# hand_master_v0.net
KiCad netlist of a schematic drawn in EAGLE
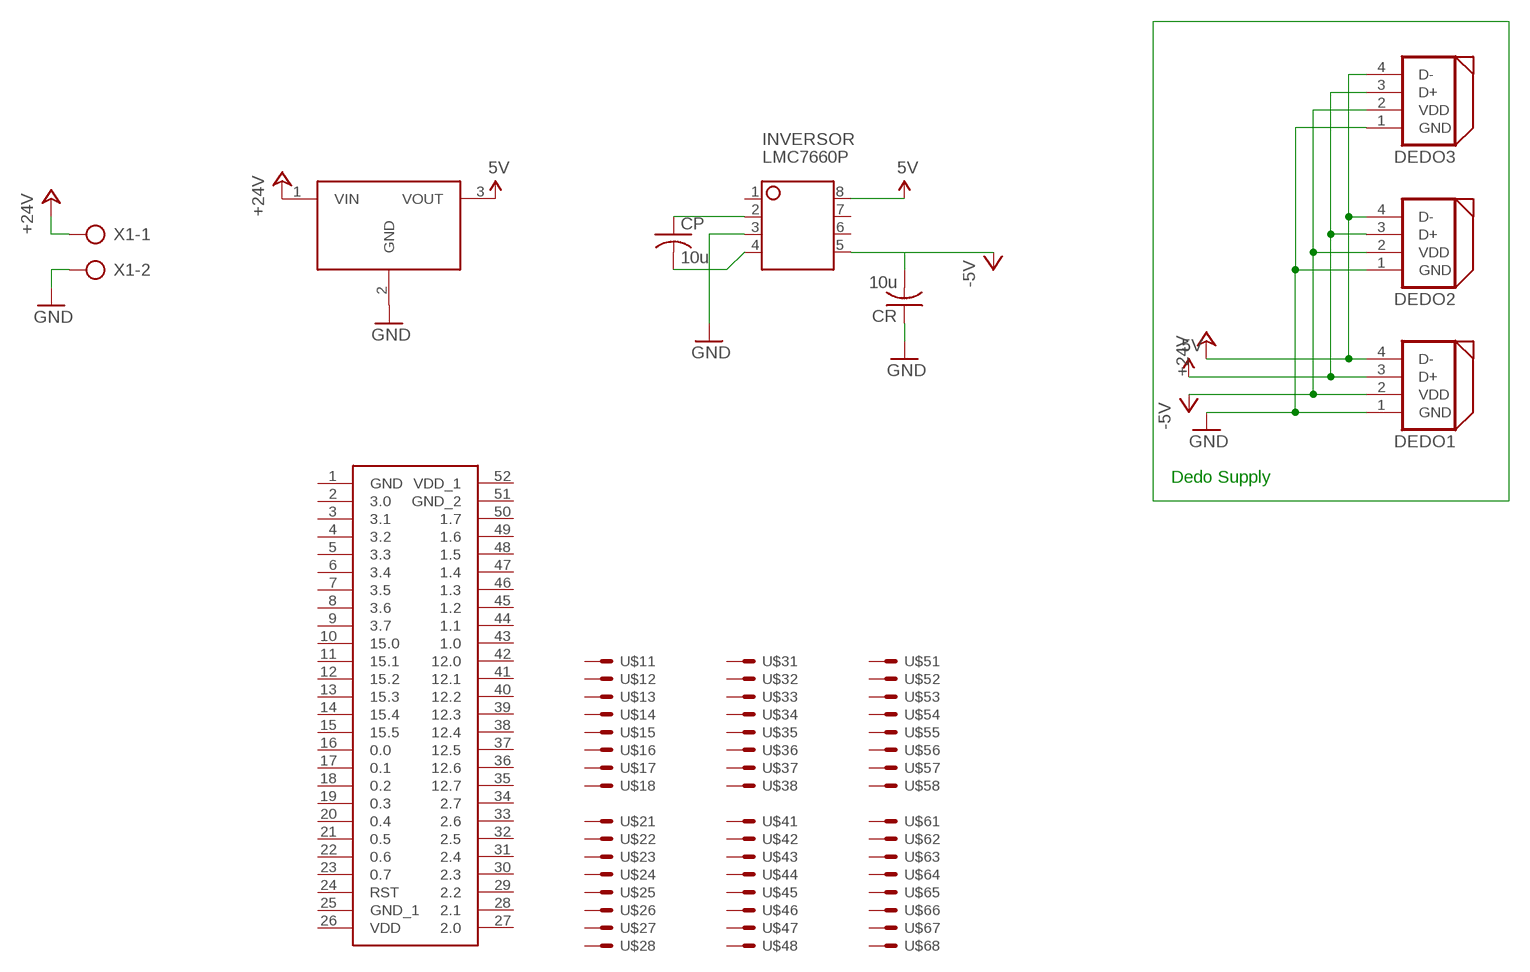
[diagram p0: schematic, sheet 1]

(export (version "E")
  (design (tool "Eeschema 10.0.6"))
  (components
    (comp (ref "CP")
      (value "10u")
      (footprint "eagle-import:C025-025X050")
      (libsource (lib "eagle-import") (part "C-US025-025X050"))
    )
    (comp (ref "CR")
      (value "10u")
      (footprint "eagle-import:C025-025X050")
      (libsource (lib "eagle-import") (part "C-US025-025X050"))
    )
    (comp (ref "DEDO1")
      (value "DYNAMIXEL_RS485")
      (footprint "eagle-import:DYNAMIXEL_SPOX_04")
      (libsource (lib "eagle-import") (part "DYNAMIXEL_RS485"))
    )
    (comp (ref "DEDO2")
      (value "DYNAMIXEL_RS485")
      (footprint "eagle-import:DYNAMIXEL_SPOX_04")
      (libsource (lib "eagle-import") (part "DYNAMIXEL_RS485"))
    )
    (comp (ref "DEDO3")
      (value "DYNAMIXEL_RS485")
      (footprint "eagle-import:DYNAMIXEL_SPOX_04")
      (libsource (lib "eagle-import") (part "DYNAMIXEL_RS485"))
    )
    (comp (ref "INVERSOR")
      (value "LMC7660P")
      (footprint "eagle-import:DIL08")
      (libsource (lib "eagle-import") (part "LMC7660P"))
    )
    (comp (ref "POWER_SUPPLY")
      (value "TSR-1")
      (footprint "eagle-import:TO220V")
      (libsource (lib "eagle-import") (part "TSR-1"))
    )
    (comp (ref "U$1")
      (value "JST8")
      (footprint "eagle-import:JST")
      (libsource (lib "eagle-import") (part "JST8"))
    )
    (comp (ref "U$2")
      (value "JST8")
      (footprint "eagle-import:JST")
      (libsource (lib "eagle-import") (part "JST8"))
    )
    (comp (ref "U$3")
      (value "JST8")
      (footprint "eagle-import:JST")
      (libsource (lib "eagle-import") (part "JST8"))
    )
    (comp (ref "U$4")
      (value "JST8")
      (footprint "eagle-import:JST")
      (libsource (lib "eagle-import") (part "JST8"))
    )
    (comp (ref "U$5")
      (value "JST8")
      (footprint "eagle-import:JST")
      (libsource (lib "eagle-import") (part "JST8"))
    )
    (comp (ref "U$6")
      (value "JST8")
      (footprint "eagle-import:JST")
      (libsource (lib "eagle-import") (part "JST8"))
    )
    (comp (ref "U$7")
      (value "CY8CKIT-059")
      (footprint "eagle-import:CY8CKIT-059")
      (libsource (lib "eagle-import") (part "CY8CKIT-059"))
    )
    (comp (ref "X1")
      (value "AK500/2")
      (footprint "eagle-import:AK500_2")
      (libsource (lib "eagle-import") (part "AK500/2"))
    )
  )
  (nets
    (net (code "1") (name "+24V") (class "Default")
      (node (ref "DEDO1") (pin "4") (pinfunction "D-_4") (pintype "bidirectional"))
      (node (ref "DEDO2") (pin "4") (pinfunction "D-_4") (pintype "bidirectional"))
      (node (ref "DEDO3") (pin "4") (pinfunction "D-_4") (pintype "bidirectional"))
      (node (ref "POWER_SUPPLY") (pin "1") (pinfunction "VIN_1") (pintype "bidirectional"))
      (node (ref "X1") (pin "1") (pinfunction "KL_1") (pintype "passive"))
    )
    (net (code "2") (name "-5V") (class "Default")
      (node (ref "CR") (pin "2") (pinfunction "2_2") (pintype "passive"))
      (node (ref "DEDO1") (pin "2") (pinfunction "VDD_2") (pintype "power_in"))
      (node (ref "DEDO2") (pin "2") (pinfunction "VDD_2") (pintype "power_in"))
      (node (ref "DEDO3") (pin "2") (pinfunction "VDD_2") (pintype "power_in"))
      (node (ref "INVERSOR") (pin "5") (pinfunction "VOUT_5") (pintype "bidirectional"))
    )
    (net (code "3") (name "5V") (class "Default")
      (node (ref "DEDO1") (pin "3") (pinfunction "D+_3") (pintype "bidirectional"))
      (node (ref "DEDO2") (pin "3") (pinfunction "D+_3") (pintype "bidirectional"))
      (node (ref "DEDO3") (pin "3") (pinfunction "D+_3") (pintype "bidirectional"))
      (node (ref "INVERSOR") (pin "8") (pinfunction "V+_8") (pintype "bidirectional"))
      (node (ref "POWER_SUPPLY") (pin "3") (pinfunction "VOUT_3") (pintype "bidirectional"))
    )
    (net (code "4") (name "GND") (class "Default")
      (node (ref "CR") (pin "1") (pinfunction "1_1") (pintype "passive"))
      (node (ref "DEDO1") (pin "1") (pinfunction "GND_1") (pintype "power_in"))
      (node (ref "DEDO2") (pin "1") (pinfunction "GND_1") (pintype "power_in"))
      (node (ref "DEDO3") (pin "1") (pinfunction "GND_1") (pintype "power_in"))
      (node (ref "INVERSOR") (pin "3") (pinfunction "GND_3") (pintype "bidirectional"))
      (node (ref "POWER_SUPPLY") (pin "2") (pinfunction "GND_2") (pintype "bidirectional"))
      (node (ref "X1") (pin "2") (pinfunction "KL_2") (pintype "passive"))
    )
    (net (code "5") (name "Net-(INVERSOR-CAP+)") (class "Default")
      (node (ref "CP") (pin "1") (pinfunction "1_1") (pintype "passive"))
      (node (ref "INVERSOR") (pin "2") (pinfunction "CAP+_2") (pintype "bidirectional"))
    )
    (net (code "6") (name "Net-(INVERSOR-CAP-)") (class "Default")
      (node (ref "CP") (pin "2") (pinfunction "2_2") (pintype "passive"))
      (node (ref "INVERSOR") (pin "4") (pinfunction "CAP-_4") (pintype "bidirectional"))
    )
    (net (code "7") (name "unconnected-(INVERSOR-LV-Pad6)") (class "Default")
      (node (ref "INVERSOR") (pin "6") (pinfunction "LV_6") (pintype "bidirectional"))
    )
    (net (code "8") (name "unconnected-(INVERSOR-N{slash}C-Pad1)") (class "Default")
      (node (ref "INVERSOR") (pin "1") (pinfunction "N/C_1") (pintype "bidirectional"))
    )
    (net (code "9") (name "unconnected-(INVERSOR-OSC-Pad7)") (class "Default")
      (node (ref "INVERSOR") (pin "7") (pinfunction "OSC_7") (pintype "bidirectional"))
    )
    (net (code "10") (name "unconnected-(U$1A-S-Pad1)") (class "Default")
      (node (ref "U$1") (pin "1") (pinfunction "S_1") (pintype "passive"))
    )
    (net (code "11") (name "unconnected-(U$1B-S-Pad2)") (class "Default")
      (node (ref "U$1") (pin "2") (pinfunction "S_2") (pintype "passive"))
    )
    (net (code "12") (name "unconnected-(U$1C-S-Pad3)") (class "Default")
      (node (ref "U$1") (pin "3") (pinfunction "S_3") (pintype "passive"))
    )
    (net (code "13") (name "unconnected-(U$1D-S-Pad4)") (class "Default")
      (node (ref "U$1") (pin "4") (pinfunction "S_4") (pintype "passive"))
    )
    (net (code "14") (name "unconnected-(U$1E-S-Pad5)") (class "Default")
      (node (ref "U$1") (pin "5") (pinfunction "S_5") (pintype "passive"))
    )
    (net (code "15") (name "unconnected-(U$1F-S-Pad6)") (class "Default")
      (node (ref "U$1") (pin "6") (pinfunction "S_6") (pintype "passive"))
    )
    (net (code "16") (name "unconnected-(U$1G-S-Pad7)") (class "Default")
      (node (ref "U$1") (pin "7") (pinfunction "S_7") (pintype "passive"))
    )
    (net (code "17") (name "unconnected-(U$1H-S-Pad8)") (class "Default")
      (node (ref "U$1") (pin "8") (pinfunction "S_8") (pintype "passive"))
    )
    (net (code "18") (name "unconnected-(U$2A-S-Pad1)") (class "Default")
      (node (ref "U$2") (pin "1") (pinfunction "S_1") (pintype "passive"))
    )
    (net (code "19") (name "unconnected-(U$2B-S-Pad2)") (class "Default")
      (node (ref "U$2") (pin "2") (pinfunction "S_2") (pintype "passive"))
    )
    (net (code "20") (name "unconnected-(U$2C-S-Pad3)") (class "Default")
      (node (ref "U$2") (pin "3") (pinfunction "S_3") (pintype "passive"))
    )
    (net (code "21") (name "unconnected-(U$2D-S-Pad4)") (class "Default")
      (node (ref "U$2") (pin "4") (pinfunction "S_4") (pintype "passive"))
    )
    (net (code "22") (name "unconnected-(U$2E-S-Pad5)") (class "Default")
      (node (ref "U$2") (pin "5") (pinfunction "S_5") (pintype "passive"))
    )
    (net (code "23") (name "unconnected-(U$2F-S-Pad6)") (class "Default")
      (node (ref "U$2") (pin "6") (pinfunction "S_6") (pintype "passive"))
    )
    (net (code "24") (name "unconnected-(U$2G-S-Pad7)") (class "Default")
      (node (ref "U$2") (pin "7") (pinfunction "S_7") (pintype "passive"))
    )
    (net (code "25") (name "unconnected-(U$2H-S-Pad8)") (class "Default")
      (node (ref "U$2") (pin "8") (pinfunction "S_8") (pintype "passive"))
    )
    (net (code "26") (name "unconnected-(U$3A-S-Pad1)") (class "Default")
      (node (ref "U$3") (pin "1") (pinfunction "S_1") (pintype "passive"))
    )
    (net (code "27") (name "unconnected-(U$3B-S-Pad2)") (class "Default")
      (node (ref "U$3") (pin "2") (pinfunction "S_2") (pintype "passive"))
    )
    (net (code "28") (name "unconnected-(U$3C-S-Pad3)") (class "Default")
      (node (ref "U$3") (pin "3") (pinfunction "S_3") (pintype "passive"))
    )
    (net (code "29") (name "unconnected-(U$3D-S-Pad4)") (class "Default")
      (node (ref "U$3") (pin "4") (pinfunction "S_4") (pintype "passive"))
    )
    (net (code "30") (name "unconnected-(U$3E-S-Pad5)") (class "Default")
      (node (ref "U$3") (pin "5") (pinfunction "S_5") (pintype "passive"))
    )
    (net (code "31") (name "unconnected-(U$3F-S-Pad6)") (class "Default")
      (node (ref "U$3") (pin "6") (pinfunction "S_6") (pintype "passive"))
    )
    (net (code "32") (name "unconnected-(U$3G-S-Pad7)") (class "Default")
      (node (ref "U$3") (pin "7") (pinfunction "S_7") (pintype "passive"))
    )
    (net (code "33") (name "unconnected-(U$3H-S-Pad8)") (class "Default")
      (node (ref "U$3") (pin "8") (pinfunction "S_8") (pintype "passive"))
    )
    (net (code "34") (name "unconnected-(U$4A-S-Pad1)") (class "Default")
      (node (ref "U$4") (pin "1") (pinfunction "S_1") (pintype "passive"))
    )
    (net (code "35") (name "unconnected-(U$4B-S-Pad2)") (class "Default")
      (node (ref "U$4") (pin "2") (pinfunction "S_2") (pintype "passive"))
    )
    (net (code "36") (name "unconnected-(U$4C-S-Pad3)") (class "Default")
      (node (ref "U$4") (pin "3") (pinfunction "S_3") (pintype "passive"))
    )
    (net (code "37") (name "unconnected-(U$4D-S-Pad4)") (class "Default")
      (node (ref "U$4") (pin "4") (pinfunction "S_4") (pintype "passive"))
    )
    (net (code "38") (name "unconnected-(U$4E-S-Pad5)") (class "Default")
      (node (ref "U$4") (pin "5") (pinfunction "S_5") (pintype "passive"))
    )
    (net (code "39") (name "unconnected-(U$4F-S-Pad6)") (class "Default")
      (node (ref "U$4") (pin "6") (pinfunction "S_6") (pintype "passive"))
    )
    (net (code "40") (name "unconnected-(U$4G-S-Pad7)") (class "Default")
      (node (ref "U$4") (pin "7") (pinfunction "S_7") (pintype "passive"))
    )
    (net (code "41") (name "unconnected-(U$4H-S-Pad8)") (class "Default")
      (node (ref "U$4") (pin "8") (pinfunction "S_8") (pintype "passive"))
    )
    (net (code "42") (name "unconnected-(U$5A-S-Pad1)") (class "Default")
      (node (ref "U$5") (pin "1") (pinfunction "S_1") (pintype "passive"))
    )
    (net (code "43") (name "unconnected-(U$5B-S-Pad2)") (class "Default")
      (node (ref "U$5") (pin "2") (pinfunction "S_2") (pintype "passive"))
    )
    (net (code "44") (name "unconnected-(U$5C-S-Pad3)") (class "Default")
      (node (ref "U$5") (pin "3") (pinfunction "S_3") (pintype "passive"))
    )
    (net (code "45") (name "unconnected-(U$5D-S-Pad4)") (class "Default")
      (node (ref "U$5") (pin "4") (pinfunction "S_4") (pintype "passive"))
    )
    (net (code "46") (name "unconnected-(U$5E-S-Pad5)") (class "Default")
      (node (ref "U$5") (pin "5") (pinfunction "S_5") (pintype "passive"))
    )
    (net (code "47") (name "unconnected-(U$5F-S-Pad6)") (class "Default")
      (node (ref "U$5") (pin "6") (pinfunction "S_6") (pintype "passive"))
    )
    (net (code "48") (name "unconnected-(U$5G-S-Pad7)") (class "Default")
      (node (ref "U$5") (pin "7") (pinfunction "S_7") (pintype "passive"))
    )
    (net (code "49") (name "unconnected-(U$5H-S-Pad8)") (class "Default")
      (node (ref "U$5") (pin "8") (pinfunction "S_8") (pintype "passive"))
    )
    (net (code "50") (name "unconnected-(U$6A-S-Pad1)") (class "Default")
      (node (ref "U$6") (pin "1") (pinfunction "S_1") (pintype "passive"))
    )
    (net (code "51") (name "unconnected-(U$6B-S-Pad2)") (class "Default")
      (node (ref "U$6") (pin "2") (pinfunction "S_2") (pintype "passive"))
    )
    (net (code "52") (name "unconnected-(U$6C-S-Pad3)") (class "Default")
      (node (ref "U$6") (pin "3") (pinfunction "S_3") (pintype "passive"))
    )
    (net (code "53") (name "unconnected-(U$6D-S-Pad4)") (class "Default")
      (node (ref "U$6") (pin "4") (pinfunction "S_4") (pintype "passive"))
    )
    (net (code "54") (name "unconnected-(U$6E-S-Pad5)") (class "Default")
      (node (ref "U$6") (pin "5") (pinfunction "S_5") (pintype "passive"))
    )
    (net (code "55") (name "unconnected-(U$6F-S-Pad6)") (class "Default")
      (node (ref "U$6") (pin "6") (pinfunction "S_6") (pintype "passive"))
    )
    (net (code "56") (name "unconnected-(U$6G-S-Pad7)") (class "Default")
      (node (ref "U$6") (pin "7") (pinfunction "S_7") (pintype "passive"))
    )
    (net (code "57") (name "unconnected-(U$6H-S-Pad8)") (class "Default")
      (node (ref "U$6") (pin "8") (pinfunction "S_8") (pintype "passive"))
    )
    (net (code "58") (name "unconnected-(U$7-0.0-Pad16)") (class "Default")
      (node (ref "U$7") (pin "16") (pinfunction "0.0_16") (pintype "bidirectional"))
    )
    (net (code "59") (name "unconnected-(U$7-0.1-Pad17)") (class "Default")
      (node (ref "U$7") (pin "17") (pinfunction "0.1_17") (pintype "bidirectional"))
    )
    (net (code "60") (name "unconnected-(U$7-0.2-Pad18)") (class "Default")
      (node (ref "U$7") (pin "18") (pinfunction "0.2_18") (pintype "bidirectional"))
    )
    (net (code "61") (name "unconnected-(U$7-0.3-Pad19)") (class "Default")
      (node (ref "U$7") (pin "19") (pinfunction "0.3_19") (pintype "bidirectional"))
    )
    (net (code "62") (name "unconnected-(U$7-0.4-Pad20)") (class "Default")
      (node (ref "U$7") (pin "20") (pinfunction "0.4_20") (pintype "bidirectional"))
    )
    (net (code "63") (name "unconnected-(U$7-0.5-Pad21)") (class "Default")
      (node (ref "U$7") (pin "21") (pinfunction "0.5_21") (pintype "bidirectional"))
    )
    (net (code "64") (name "unconnected-(U$7-0.6-Pad22)") (class "Default")
      (node (ref "U$7") (pin "22") (pinfunction "0.6_22") (pintype "bidirectional"))
    )
    (net (code "65") (name "unconnected-(U$7-0.7-Pad23)") (class "Default")
      (node (ref "U$7") (pin "23") (pinfunction "0.7_23") (pintype "bidirectional"))
    )
    (net (code "66") (name "unconnected-(U$7-1.0-Pad43)") (class "Default")
      (node (ref "U$7") (pin "43") (pinfunction "1.0_43") (pintype "bidirectional"))
    )
    (net (code "67") (name "unconnected-(U$7-1.1-Pad44)") (class "Default")
      (node (ref "U$7") (pin "44") (pinfunction "1.1_44") (pintype "bidirectional"))
    )
    (net (code "68") (name "unconnected-(U$7-1.2-Pad45)") (class "Default")
      (node (ref "U$7") (pin "45") (pinfunction "1.2_45") (pintype "bidirectional"))
    )
    (net (code "69") (name "unconnected-(U$7-1.3-Pad46)") (class "Default")
      (node (ref "U$7") (pin "46") (pinfunction "1.3_46") (pintype "bidirectional"))
    )
    (net (code "70") (name "unconnected-(U$7-1.4-Pad47)") (class "Default")
      (node (ref "U$7") (pin "47") (pinfunction "1.4_47") (pintype "bidirectional"))
    )
    (net (code "71") (name "unconnected-(U$7-1.5-Pad48)") (class "Default")
      (node (ref "U$7") (pin "48") (pinfunction "1.5_48") (pintype "bidirectional"))
    )
    (net (code "72") (name "unconnected-(U$7-1.6-Pad49)") (class "Default")
      (node (ref "U$7") (pin "49") (pinfunction "1.6_49") (pintype "bidirectional"))
    )
    (net (code "73") (name "unconnected-(U$7-1.7-Pad50)") (class "Default")
      (node (ref "U$7") (pin "50") (pinfunction "1.7_50") (pintype "bidirectional"))
    )
    (net (code "74") (name "unconnected-(U$7-2.0-Pad27)") (class "Default")
      (node (ref "U$7") (pin "27") (pinfunction "2.0_27") (pintype "bidirectional"))
    )
    (net (code "75") (name "unconnected-(U$7-2.1-Pad28)") (class "Default")
      (node (ref "U$7") (pin "28") (pinfunction "2.1_28") (pintype "bidirectional"))
    )
    (net (code "76") (name "unconnected-(U$7-2.2-Pad29)") (class "Default")
      (node (ref "U$7") (pin "29") (pinfunction "2.2_29") (pintype "bidirectional"))
    )
    (net (code "77") (name "unconnected-(U$7-2.3-Pad30)") (class "Default")
      (node (ref "U$7") (pin "30") (pinfunction "2.3_30") (pintype "bidirectional"))
    )
    (net (code "78") (name "unconnected-(U$7-2.4-Pad31)") (class "Default")
      (node (ref "U$7") (pin "31") (pinfunction "2.4_31") (pintype "bidirectional"))
    )
    (net (code "79") (name "unconnected-(U$7-2.5-Pad32)") (class "Default")
      (node (ref "U$7") (pin "32") (pinfunction "2.5_32") (pintype "bidirectional"))
    )
    (net (code "80") (name "unconnected-(U$7-2.6-Pad33)") (class "Default")
      (node (ref "U$7") (pin "33") (pinfunction "2.6_33") (pintype "bidirectional"))
    )
    (net (code "81") (name "unconnected-(U$7-2.7-Pad34)") (class "Default")
      (node (ref "U$7") (pin "34") (pinfunction "2.7_34") (pintype "bidirectional"))
    )
    (net (code "82") (name "unconnected-(U$7-3.0-Pad2)") (class "Default")
      (node (ref "U$7") (pin "2") (pinfunction "3.0_2") (pintype "bidirectional"))
    )
    (net (code "83") (name "unconnected-(U$7-3.1-Pad3)") (class "Default")
      (node (ref "U$7") (pin "3") (pinfunction "3.1_3") (pintype "bidirectional"))
    )
    (net (code "84") (name "unconnected-(U$7-3.2-Pad4)") (class "Default")
      (node (ref "U$7") (pin "4") (pinfunction "3.2_4") (pintype "bidirectional"))
    )
    (net (code "85") (name "unconnected-(U$7-3.3-Pad5)") (class "Default")
      (node (ref "U$7") (pin "5") (pinfunction "3.3_5") (pintype "bidirectional"))
    )
    (net (code "86") (name "unconnected-(U$7-3.4-Pad6)") (class "Default")
      (node (ref "U$7") (pin "6") (pinfunction "3.4_6") (pintype "bidirectional"))
    )
    (net (code "87") (name "unconnected-(U$7-3.5-Pad7)") (class "Default")
      (node (ref "U$7") (pin "7") (pinfunction "3.5_7") (pintype "bidirectional"))
    )
    (net (code "88") (name "unconnected-(U$7-3.6-Pad8)") (class "Default")
      (node (ref "U$7") (pin "8") (pinfunction "3.6_8") (pintype "bidirectional"))
    )
    (net (code "89") (name "unconnected-(U$7-3.7-Pad9)") (class "Default")
      (node (ref "U$7") (pin "9") (pinfunction "3.7_9") (pintype "bidirectional"))
    )
    (net (code "90") (name "unconnected-(U$7-12.0-Pad42)") (class "Default")
      (node (ref "U$7") (pin "42") (pinfunction "12.0_42") (pintype "bidirectional"))
    )
    (net (code "91") (name "unconnected-(U$7-12.1-Pad41)") (class "Default")
      (node (ref "U$7") (pin "41") (pinfunction "12.1_41") (pintype "bidirectional"))
    )
    (net (code "92") (name "unconnected-(U$7-12.2-Pad40)") (class "Default")
      (node (ref "U$7") (pin "40") (pinfunction "12.2_40") (pintype "bidirectional"))
    )
    (net (code "93") (name "unconnected-(U$7-12.3-Pad39)") (class "Default")
      (node (ref "U$7") (pin "39") (pinfunction "12.3_39") (pintype "bidirectional"))
    )
    (net (code "94") (name "unconnected-(U$7-12.4-Pad38)") (class "Default")
      (node (ref "U$7") (pin "38") (pinfunction "12.4_38") (pintype "bidirectional"))
    )
    (net (code "95") (name "unconnected-(U$7-12.5-Pad37)") (class "Default")
      (node (ref "U$7") (pin "37") (pinfunction "12.5_37") (pintype "bidirectional"))
    )
    (net (code "96") (name "unconnected-(U$7-12.6-Pad36)") (class "Default")
      (node (ref "U$7") (pin "36") (pinfunction "12.6_36") (pintype "bidirectional"))
    )
    (net (code "97") (name "unconnected-(U$7-12.7-Pad35)") (class "Default")
      (node (ref "U$7") (pin "35") (pinfunction "12.7_35") (pintype "bidirectional"))
    )
    (net (code "98") (name "unconnected-(U$7-15.0-Pad10)") (class "Default")
      (node (ref "U$7") (pin "10") (pinfunction "15.0_10") (pintype "bidirectional"))
    )
    (net (code "99") (name "unconnected-(U$7-15.1-Pad11)") (class "Default")
      (node (ref "U$7") (pin "11") (pinfunction "15.1_11") (pintype "bidirectional"))
    )
    (net (code "100") (name "unconnected-(U$7-15.2-Pad12)") (class "Default")
      (node (ref "U$7") (pin "12") (pinfunction "15.2_12") (pintype "bidirectional"))
    )
    (net (code "101") (name "unconnected-(U$7-15.3-Pad13)") (class "Default")
      (node (ref "U$7") (pin "13") (pinfunction "15.3_13") (pintype "bidirectional"))
    )
    (net (code "102") (name "unconnected-(U$7-15.4-Pad14)") (class "Default")
      (node (ref "U$7") (pin "14") (pinfunction "15.4_14") (pintype "bidirectional"))
    )
    (net (code "103") (name "unconnected-(U$7-15.5-Pad15)") (class "Default")
      (node (ref "U$7") (pin "15") (pinfunction "15.5_15") (pintype "bidirectional"))
    )
    (net (code "104") (name "unconnected-(U$7-GND-Pad1)") (class "Default")
      (node (ref "U$7") (pin "1") (pinfunction "GND_1") (pintype "bidirectional"))
    )
    (net (code "105") (name "unconnected-(U$7-GND_1-Pad25)") (class "Default")
      (node (ref "U$7") (pin "25") (pinfunction "GND_1_25") (pintype "bidirectional"))
    )
    (net (code "106") (name "unconnected-(U$7-GND_2-Pad51)") (class "Default")
      (node (ref "U$7") (pin "51") (pinfunction "GND_2_51") (pintype "bidirectional"))
    )
    (net (code "107") (name "unconnected-(U$7-RST-Pad24)") (class "Default")
      (node (ref "U$7") (pin "24") (pinfunction "RST_24") (pintype "bidirectional"))
    )
    (net (code "108") (name "unconnected-(U$7-VDD-Pad26)") (class "Default")
      (node (ref "U$7") (pin "26") (pinfunction "VDD_26") (pintype "bidirectional"))
    )
    (net (code "109") (name "unconnected-(U$7-VDD_1-Pad52)") (class "Default")
      (node (ref "U$7") (pin "52") (pinfunction "VDD_1_52") (pintype "bidirectional"))
    )
  )
)
